# ION-KB_Bluetooth_LiPo.net
KiCad netlist of a schematic drawn in EAGLE
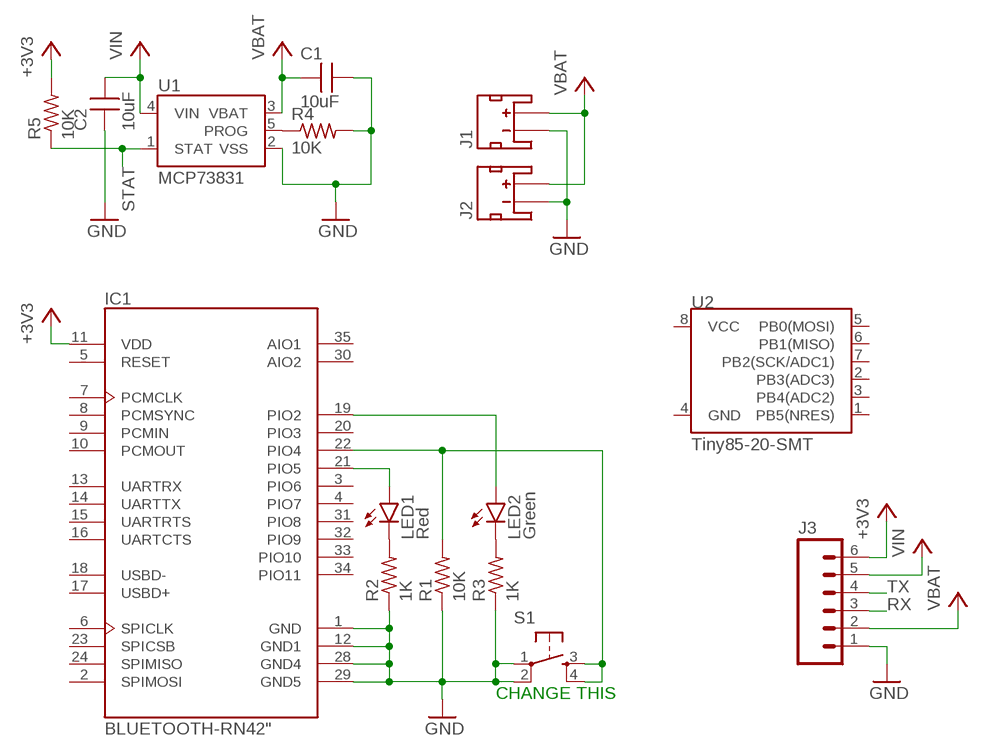
[diagram p0: schematic, sheet 1]

(export (version "E")
  (design (tool "Eeschema 10.0.6"))
  (components
    (comp (ref "C1")
      (value "10uF")
      (footprint "eagle-import:C0603")
      (libsource (lib "eagle-import") (part "CAPACITOR0603"))
    )
    (comp (ref "C2")
      (value "10uF")
      (footprint "eagle-import:C0603")
      (libsource (lib "eagle-import") (part "CAPACITOR0603"))
    )
    (comp (ref "IC1")
      (value "BLUETOOTH-RN42\"")
      (footprint "eagle-import:RN42")
      (libsource (lib "eagle-import") (part "BLUETOOTH-RN42{dblquote}"))
    )
    (comp (ref "J1")
      (value "JST_2MM_MALE")
      (footprint "eagle-import:JST-2-SMD")
      (libsource (lib "eagle-import") (part "JST_2MM_MALE"))
    )
    (comp (ref "J2")
      (value "JST_2MM_MALE")
      (footprint "eagle-import:JST-2-SMD")
      (libsource (lib "eagle-import") (part "JST_2MM_MALE"))
    )
    (comp (ref "J3")
      (value "1X06M-0.05-PTH")
      (footprint "eagle-import:M-1X06-0.05-PTH")
      (libsource (lib "eagle-import") (part "1X06M-0.05-PTH"))
    )
    (comp (ref "LED1")
      (value "Red")
      (footprint "eagle-import:L0603")
      (libsource (lib "eagle-import") (part "LED0603"))
    )
    (comp (ref "LED2")
      (value "Green")
      (footprint "eagle-import:L0603")
      (libsource (lib "eagle-import") (part "LED0603"))
    )
    (comp (ref "R1")
      (value "10K")
      (footprint "eagle-import:R0603")
      (libsource (lib "eagle-import") (part "RESISTOR0603"))
    )
    (comp (ref "R2")
      (value "1K")
      (footprint "eagle-import:R0603")
      (libsource (lib "eagle-import") (part "RESISTOR0603"))
    )
    (comp (ref "R3")
      (value "1K")
      (footprint "eagle-import:R0603")
      (libsource (lib "eagle-import") (part "RESISTOR0603"))
    )
    (comp (ref "R4")
      (value "10K")
      (footprint "eagle-import:R0603")
      (libsource (lib "eagle-import") (part "RESISTOR0603"))
    )
    (comp (ref "R5")
      (value "10K")
      (footprint "eagle-import:R0603")
      (libsource (lib "eagle-import") (part "RESISTOR0603"))
    )
    (comp (ref "S1")
      (value "SWITCH-TACTILESMD")
      (footprint "eagle-import:SWITCH-TACTILE-SMD")
      (libsource (lib "eagle-import") (part "SWITCH-TACTILESMD"))
    )
    (comp (ref "U1")
      (value "MCP73831")
      (footprint "eagle-import:SOT23-5")
      (libsource (lib "eagle-import") (part "MCP73831"))
    )
    (comp (ref "U2")
      (value "Tiny85-20-SMT")
      (footprint "eagle-import:SO08-EIAJ")
      (libsource (lib "eagle-import") (part "ATTINY45TINY85-20-SMT"))
    )
  )
  (nets
    (net (code "1") (name "+3V3") (class "Default")
      (node (ref "IC1") (pin "11") (pinfunction "VDD_11") (pintype "power_in"))
      (node (ref "J3") (pin "6") (pinfunction "6_6") (pintype "passive"))
      (node (ref "R5") (pin "2") (pinfunction "2_2") (pintype "passive"))
    )
    (net (code "2") (name "/RX") (class "Default")
      (node (ref "J3") (pin "3") (pinfunction "3_3") (pintype "passive"))
    )
    (net (code "3") (name "/STAT") (class "Default")
      (node (ref "R5") (pin "1") (pinfunction "1_1") (pintype "passive"))
      (node (ref "U1") (pin "1") (pinfunction "STAT_1") (pintype "output"))
    )
    (net (code "4") (name "/TX") (class "Default")
      (node (ref "J3") (pin "4") (pinfunction "4_4") (pintype "passive"))
    )
    (net (code "5") (name "GND") (class "Default")
      (node (ref "C1") (pin "2") (pinfunction "2_2") (pintype "passive"))
      (node (ref "C2") (pin "1") (pinfunction "1_1") (pintype "passive"))
      (node (ref "IC1") (pin "1") (pinfunction "GND_1") (pintype "power_in"))
      (node (ref "IC1") (pin "12") (pinfunction "GND1_12") (pintype "power_in"))
      (node (ref "IC1") (pin "28") (pinfunction "GND4_28") (pintype "power_in"))
      (node (ref "IC1") (pin "29") (pinfunction "GND5_29") (pintype "power_in"))
      (node (ref "J1") (pin "1") (pinfunction "-_1") (pintype "bidirectional"))
      (node (ref "J2") (pin "1") (pinfunction "-_1") (pintype "bidirectional"))
      (node (ref "J3") (pin "1") (pinfunction "1_1") (pintype "passive"))
      (node (ref "R1") (pin "1") (pinfunction "1_1") (pintype "passive"))
      (node (ref "R2") (pin "1") (pinfunction "1_1") (pintype "passive"))
      (node (ref "R3") (pin "1") (pinfunction "1_1") (pintype "passive"))
      (node (ref "R4") (pin "2") (pinfunction "2_2") (pintype "passive"))
      (node (ref "S1") (pin "1") (pinfunction "1_1") (pintype "passive"))
      (node (ref "S1") (pin "2") (pinfunction "2_2") (pintype "passive"))
      (node (ref "U1") (pin "2") (pinfunction "VSS_2") (pintype "power_in"))
    )
    (net (code "6") (name "Net-(IC1-PIO2)") (class "Default")
      (node (ref "IC1") (pin "19") (pinfunction "PIO2_19") (pintype "bidirectional"))
      (node (ref "LED2") (pin "A") (pinfunction "A_A") (pintype "passive"))
    )
    (net (code "7") (name "Net-(IC1-PIO4)") (class "Default")
      (node (ref "IC1") (pin "22") (pinfunction "PIO4_22") (pintype "bidirectional"))
      (node (ref "R1") (pin "2") (pinfunction "2_2") (pintype "passive"))
      (node (ref "S1") (pin "3") (pinfunction "3_3") (pintype "passive"))
      (node (ref "S1") (pin "4") (pinfunction "4_4") (pintype "passive"))
    )
    (net (code "8") (name "Net-(IC1-PIO5)") (class "Default")
      (node (ref "IC1") (pin "21") (pinfunction "PIO5_21") (pintype "bidirectional"))
      (node (ref "LED1") (pin "A") (pinfunction "A_A") (pintype "passive"))
    )
    (net (code "9") (name "Net-(LED1-PadC)") (class "Default")
      (node (ref "LED1") (pin "C") (pinfunction "C_C") (pintype "passive"))
      (node (ref "R2") (pin "2") (pinfunction "2_2") (pintype "passive"))
    )
    (net (code "10") (name "Net-(LED2-PadC)") (class "Default")
      (node (ref "LED2") (pin "C") (pinfunction "C_C") (pintype "passive"))
      (node (ref "R3") (pin "2") (pinfunction "2_2") (pintype "passive"))
    )
    (net (code "11") (name "Net-(U1-PROG)") (class "Default")
      (node (ref "R4") (pin "1") (pinfunction "1_1") (pintype "passive"))
      (node (ref "U1") (pin "5") (pinfunction "PROG_5") (pintype "input"))
    )
    (net (code "12") (name "VBAT") (class "Default")
      (node (ref "C1") (pin "1") (pinfunction "1_1") (pintype "passive"))
      (node (ref "J1") (pin "2") (pinfunction "+_2") (pintype "bidirectional"))
      (node (ref "J2") (pin "2") (pinfunction "+_2") (pintype "bidirectional"))
      (node (ref "J3") (pin "2") (pinfunction "2_2") (pintype "passive"))
      (node (ref "U1") (pin "3") (pinfunction "VBAT_3") (pintype "power_in"))
    )
    (net (code "13") (name "VIN") (class "Default")
      (node (ref "C2") (pin "2") (pinfunction "2_2") (pintype "passive"))
      (node (ref "J3") (pin "5") (pinfunction "5_5") (pintype "passive"))
      (node (ref "U1") (pin "4") (pinfunction "VIN_4") (pintype "power_in"))
    )
    (net (code "14") (name "unconnected-(IC1-AIO1-Pad35)") (class "Default")
      (node (ref "IC1") (pin "35") (pinfunction "AIO1_35") (pintype "bidirectional"))
    )
    (net (code "15") (name "unconnected-(IC1-AIO2-Pad30)") (class "Default")
      (node (ref "IC1") (pin "30") (pinfunction "AIO2_30") (pintype "bidirectional"))
    )
    (net (code "16") (name "unconnected-(IC1-PCMCLK-Pad7)") (class "Default")
      (node (ref "IC1") (pin "7") (pinfunction "PCMCLK_7") (pintype "bidirectional"))
    )
    (net (code "17") (name "unconnected-(IC1-PCMIN-Pad9)") (class "Default")
      (node (ref "IC1") (pin "9") (pinfunction "PCMIN_9") (pintype "bidirectional"))
    )
    (net (code "18") (name "unconnected-(IC1-PCMOUT-Pad10)") (class "Default")
      (node (ref "IC1") (pin "10") (pinfunction "PCMOUT_10") (pintype "bidirectional"))
    )
    (net (code "19") (name "unconnected-(IC1-PCMSYNC-Pad8)") (class "Default")
      (node (ref "IC1") (pin "8") (pinfunction "PCMSYNC_8") (pintype "bidirectional"))
    )
    (net (code "20") (name "unconnected-(IC1-PIO3-Pad20)") (class "Default")
      (node (ref "IC1") (pin "20") (pinfunction "PIO3_20") (pintype "bidirectional"))
    )
    (net (code "21") (name "unconnected-(IC1-PIO6-Pad3)") (class "Default")
      (node (ref "IC1") (pin "3") (pinfunction "PIO6_3") (pintype "bidirectional"))
    )
    (net (code "22") (name "unconnected-(IC1-PIO7-Pad4)") (class "Default")
      (node (ref "IC1") (pin "4") (pinfunction "PIO7_4") (pintype "bidirectional"))
    )
    (net (code "23") (name "unconnected-(IC1-PIO8-Pad31)") (class "Default")
      (node (ref "IC1") (pin "31") (pinfunction "PIO8_31") (pintype "bidirectional"))
    )
    (net (code "24") (name "unconnected-(IC1-PIO9-Pad32)") (class "Default")
      (node (ref "IC1") (pin "32") (pinfunction "PIO9_32") (pintype "bidirectional"))
    )
    (net (code "25") (name "unconnected-(IC1-PIO10-Pad33)") (class "Default")
      (node (ref "IC1") (pin "33") (pinfunction "PIO10_33") (pintype "bidirectional"))
    )
    (net (code "26") (name "unconnected-(IC1-PIO11-Pad34)") (class "Default")
      (node (ref "IC1") (pin "34") (pinfunction "PIO11_34") (pintype "bidirectional"))
    )
    (net (code "27") (name "unconnected-(IC1-RESET-Pad5)") (class "Default")
      (node (ref "IC1") (pin "5") (pinfunction "RESET_5") (pintype "input"))
    )
    (net (code "28") (name "unconnected-(IC1-SPICLK-Pad6)") (class "Default")
      (node (ref "IC1") (pin "6") (pinfunction "SPICLK_6") (pintype "bidirectional"))
    )
    (net (code "29") (name "unconnected-(IC1-SPICSB-Pad23)") (class "Default")
      (node (ref "IC1") (pin "23") (pinfunction "SPICSB_23") (pintype "bidirectional"))
    )
    (net (code "30") (name "unconnected-(IC1-SPIMISO-Pad24)") (class "Default")
      (node (ref "IC1") (pin "24") (pinfunction "SPIMISO_24") (pintype "bidirectional"))
    )
    (net (code "31") (name "unconnected-(IC1-SPIMOSI-Pad2)") (class "Default")
      (node (ref "IC1") (pin "2") (pinfunction "SPIMOSI_2") (pintype "bidirectional"))
    )
    (net (code "32") (name "unconnected-(IC1-UARTCTS-Pad16)") (class "Default")
      (node (ref "IC1") (pin "16") (pinfunction "UARTCTS_16") (pintype "bidirectional"))
    )
    (net (code "33") (name "unconnected-(IC1-UARTRTS-Pad15)") (class "Default")
      (node (ref "IC1") (pin "15") (pinfunction "UARTRTS_15") (pintype "bidirectional"))
    )
    (net (code "34") (name "unconnected-(IC1-UARTRX-Pad13)") (class "Default")
      (node (ref "IC1") (pin "13") (pinfunction "UARTRX_13") (pintype "bidirectional"))
    )
    (net (code "35") (name "unconnected-(IC1-UARTTX-Pad14)") (class "Default")
      (node (ref "IC1") (pin "14") (pinfunction "UARTTX_14") (pintype "bidirectional"))
    )
    (net (code "36") (name "unconnected-(IC1-USBD+-Pad17)") (class "Default")
      (node (ref "IC1") (pin "17") (pinfunction "USBD+_17") (pintype "bidirectional"))
    )
    (net (code "37") (name "unconnected-(IC1-USBD--Pad18)") (class "Default")
      (node (ref "IC1") (pin "18") (pinfunction "USBD-_18") (pintype "bidirectional"))
    )
    (net (code "38") (name "unconnected-(J1-PAD1-PadNC1)") (class "Default")
      (node (ref "J1") (pin "NC1") (pinfunction "PAD1_NC1") (pintype "bidirectional"))
    )
    (net (code "39") (name "unconnected-(J1-PAD2-PadNC2)") (class "Default")
      (node (ref "J1") (pin "NC2") (pinfunction "PAD2_NC2") (pintype "bidirectional"))
    )
    (net (code "40") (name "unconnected-(J2-PAD1-PadNC1)") (class "Default")
      (node (ref "J2") (pin "NC1") (pinfunction "PAD1_NC1") (pintype "bidirectional"))
    )
    (net (code "41") (name "unconnected-(J2-PAD2-PadNC2)") (class "Default")
      (node (ref "J2") (pin "NC2") (pinfunction "PAD2_NC2") (pintype "bidirectional"))
    )
    (net (code "42") (name "unconnected-(U2-GND-Pad4)") (class "Default")
      (node (ref "U2") (pin "4") (pinfunction "GND_4") (pintype "bidirectional"))
    )
    (net (code "43") (name "unconnected-(U2-PB0(MOSI)-Pad5)") (class "Default")
      (node (ref "U2") (pin "5") (pinfunction "PB0(MOSI)_5") (pintype "bidirectional"))
    )
    (net (code "44") (name "unconnected-(U2-PB1(MISO)-Pad6)") (class "Default")
      (node (ref "U2") (pin "6") (pinfunction "PB1(MISO)_6") (pintype "bidirectional"))
    )
    (net (code "45") (name "unconnected-(U2-PB2(SCK{slash}ADC1)-Pad7)") (class "Default")
      (node (ref "U2") (pin "7") (pinfunction "PB2(SCK/ADC1)_7") (pintype "bidirectional"))
    )
    (net (code "46") (name "unconnected-(U2-PB3(ADC3)-Pad2)") (class "Default")
      (node (ref "U2") (pin "2") (pinfunction "PB3(ADC3)_2") (pintype "bidirectional"))
    )
    (net (code "47") (name "unconnected-(U2-PB4(ADC2)-Pad3)") (class "Default")
      (node (ref "U2") (pin "3") (pinfunction "PB4(ADC2)_3") (pintype "bidirectional"))
    )
    (net (code "48") (name "unconnected-(U2-PB5(NRES)-Pad1)") (class "Default")
      (node (ref "U2") (pin "1") (pinfunction "PB5(NRES)_1") (pintype "bidirectional"))
    )
    (net (code "49") (name "unconnected-(U2-VCC-Pad8)") (class "Default")
      (node (ref "U2") (pin "8") (pinfunction "VCC_8") (pintype "bidirectional"))
    )
  )
)
